# SCH_Spotify-Display_2026-06-03.net
KiCad netlist of a schematic drawn in EasyEDA
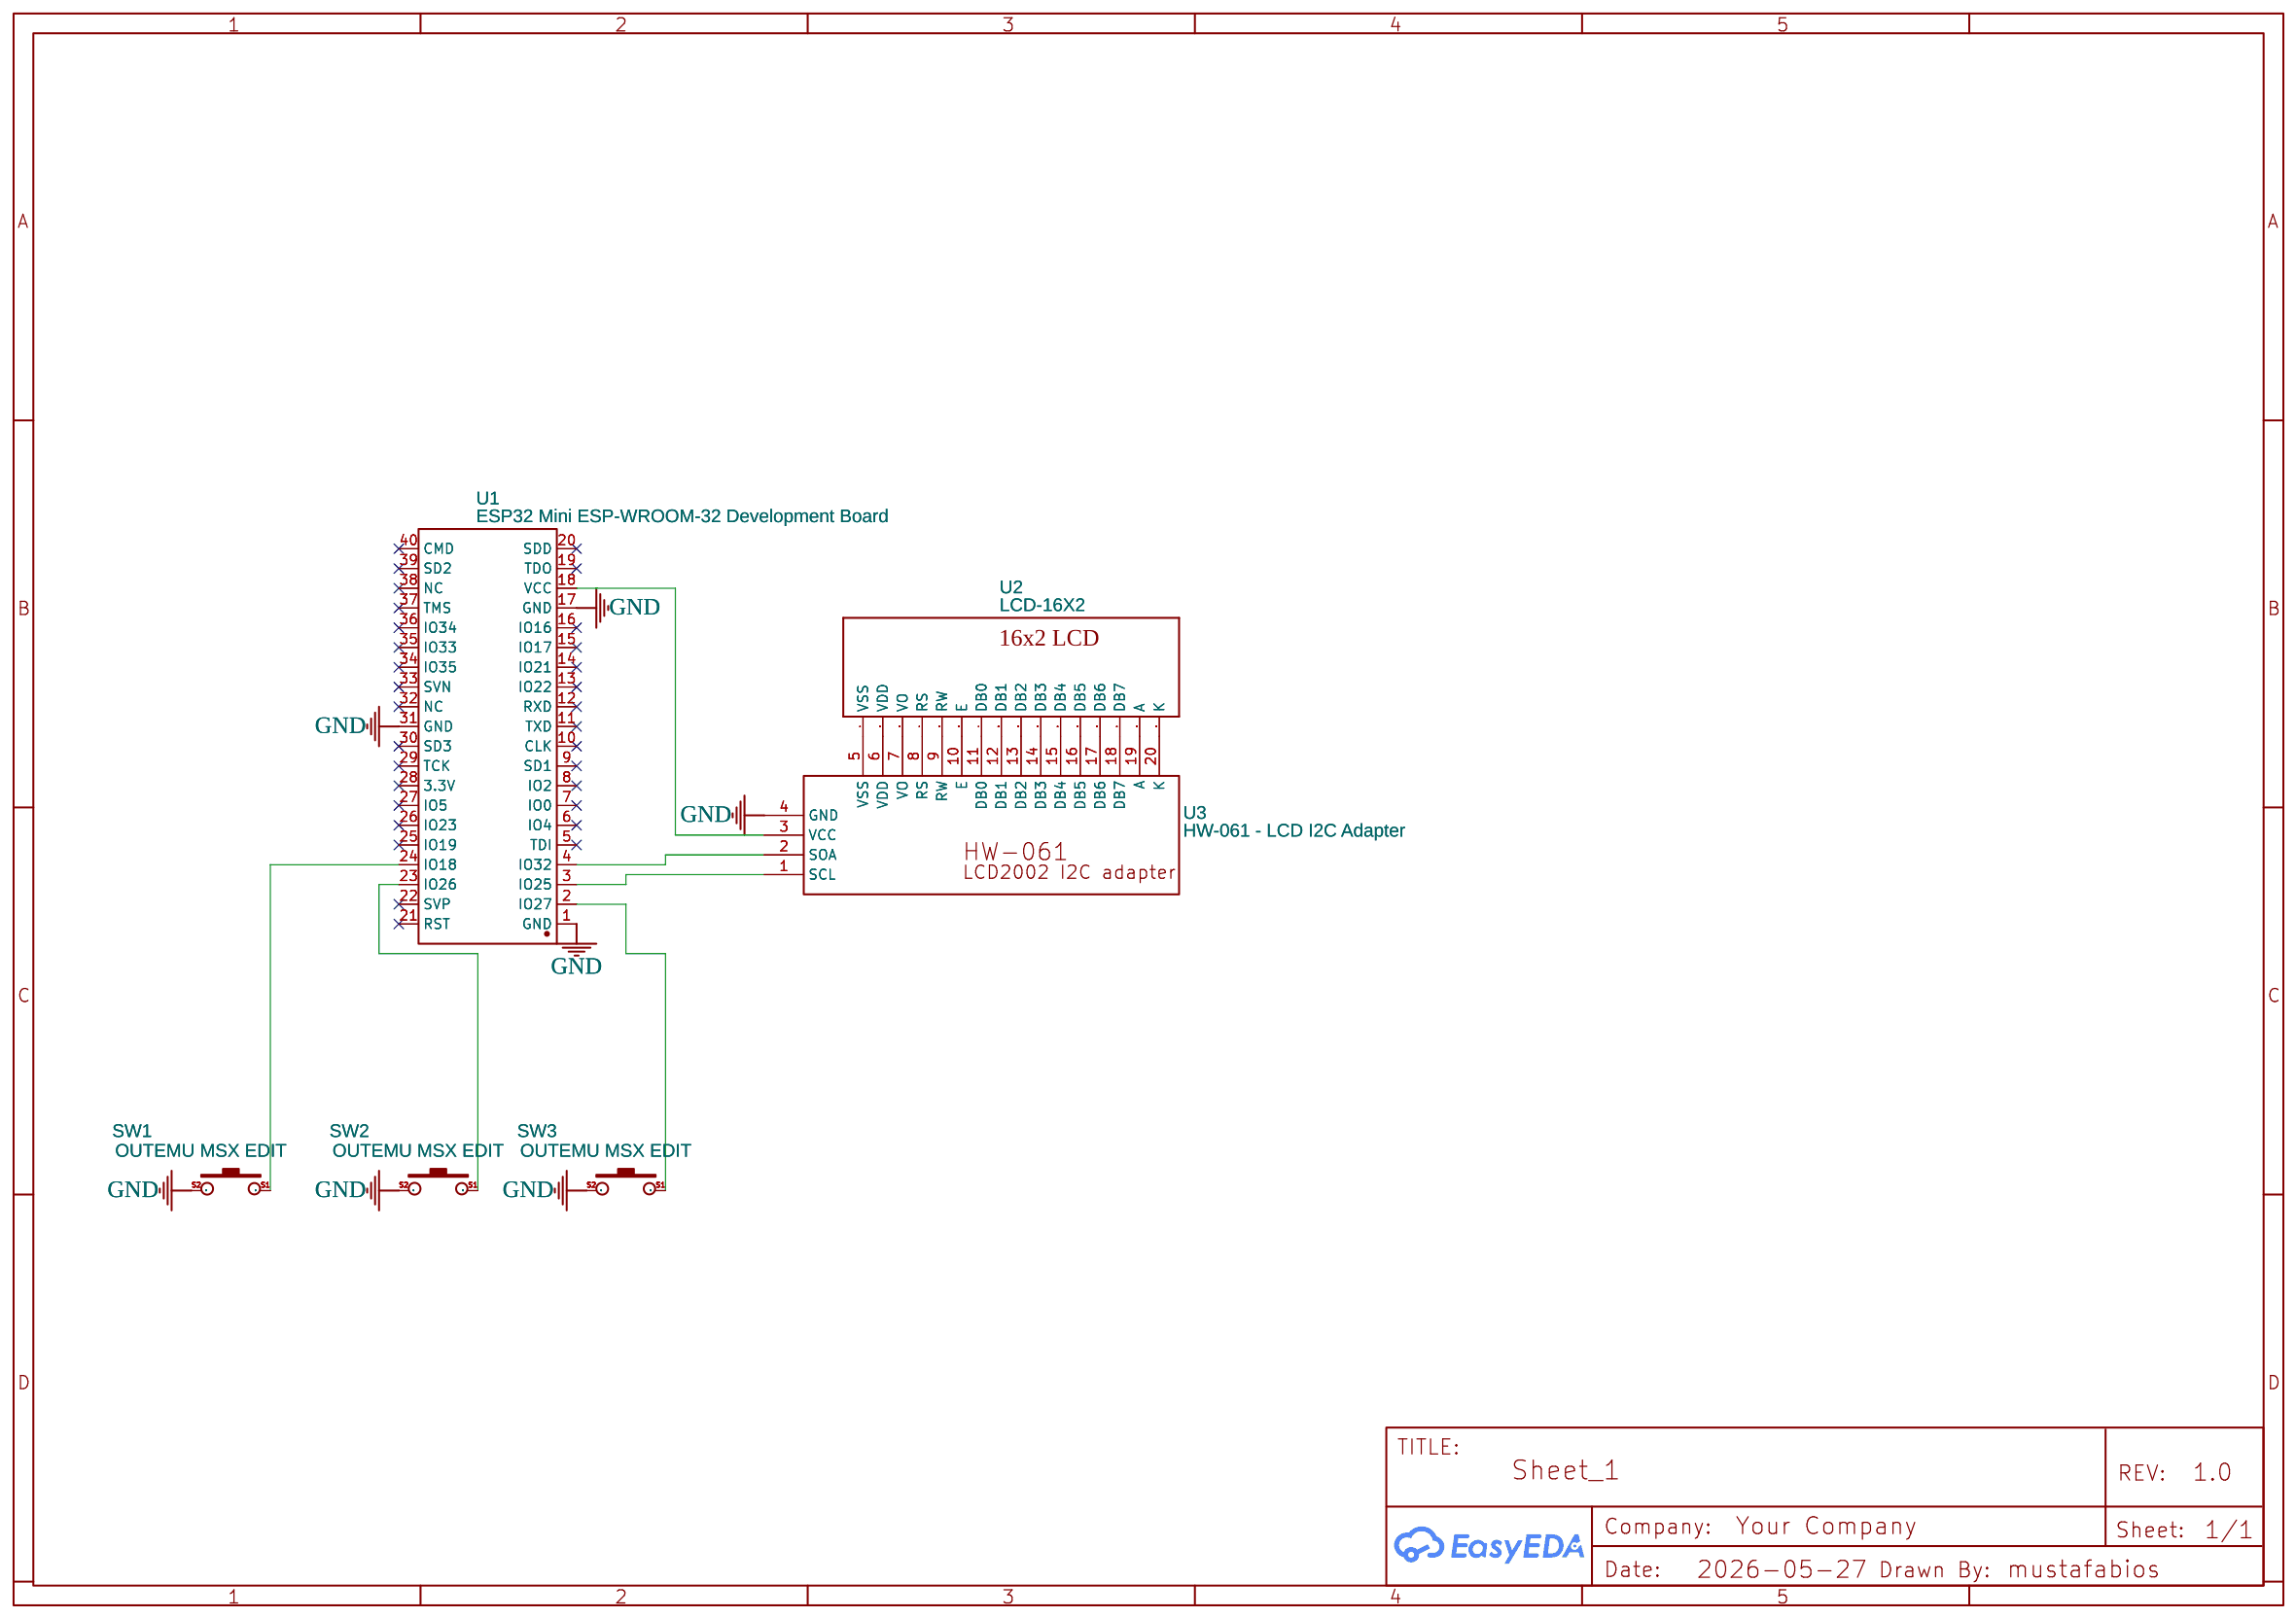
[diagram p0: schematic sheet]

(export (version "E")
  (design (tool "Eeschema 10.0.6"))
  (components
    (comp (ref "SW1") (value "OUTEMU MSX EDIT") (libsource (lib "") (part "OUTEMU MSX EDIT")))
    (comp (ref "SW2") (value "OUTEMU MSX EDIT") (libsource (lib "") (part "OUTEMU MSX EDIT")))
    (comp (ref "SW3") (value "OUTEMU MSX EDIT") (libsource (lib "") (part "OUTEMU MSX EDIT")))
    (comp (ref "U1")
      (value "ESP32 Mini ESP-WROOM-32 Development Board")
      (fields (field (name "Manufacturer Part") "B07BK435ZW") (field (name "Manufacturer") "HiLetgo"))
      (libsource (lib "") (part "ESP32 Mini ESP-WROOM-32 Development Board"))
    )
    (comp (ref "U2") (value "LCD-16X2") (libsource (lib "") (part "LCD-16X2")))
    (comp (ref "U3")
      (value "HW-061 - LCD I2C Adapter")
      (libsource (lib "") (part "HW-061 - LCD I2C Adapter"))
    )
  )
  (nets
    (net (code "1") (name "GND") (class "Default")
      (node (ref "SW1") (pin "S2") (pinfunction "S2_S2") (pintype "unspecified"))
      (node (ref "SW2") (pin "S2") (pinfunction "S2_S2") (pintype "unspecified"))
      (node (ref "SW3") (pin "S2") (pinfunction "S2_S2") (pintype "unspecified"))
      (node (ref "U1") (pin "1") (pinfunction "GND_1") (pintype "passive"))
      (node (ref "U1") (pin "17") (pinfunction "GND_17") (pintype "passive"))
      (node (ref "U1") (pin "31") (pinfunction "GND_31") (pintype "passive"))
      (node (ref "U3") (pin "4") (pinfunction "GND_4") (pintype "unspecified"))
    )
    (net (code "2") (name "Net-(U1-IO18)") (class "Default")
      (node (ref "SW1") (pin "S1") (pinfunction "S1_S1") (pintype "unspecified"))
      (node (ref "U1") (pin "24") (pinfunction "IO18_24") (pintype "bidirectional"))
    )
    (net (code "3") (name "Net-(U1-IO25)") (class "Default")
      (node (ref "U1") (pin "3") (pinfunction "IO25_3") (pintype "bidirectional"))
      (node (ref "U3") (pin "1") (pinfunction "SCL_1") (pintype "unspecified"))
    )
    (net (code "4") (name "Net-(U1-IO26)") (class "Default")
      (node (ref "SW2") (pin "S1") (pinfunction "S1_S1") (pintype "unspecified"))
      (node (ref "U1") (pin "23") (pinfunction "IO26_23") (pintype "bidirectional"))
    )
    (net (code "5") (name "Net-(U1-IO27)") (class "Default")
      (node (ref "SW3") (pin "S1") (pinfunction "S1_S1") (pintype "unspecified"))
      (node (ref "U1") (pin "2") (pinfunction "IO27_2") (pintype "bidirectional"))
    )
    (net (code "6") (name "Net-(U1-IO32)") (class "Default")
      (node (ref "U1") (pin "4") (pinfunction "IO32_4") (pintype "bidirectional"))
      (node (ref "U3") (pin "2") (pinfunction "SOA_2") (pintype "unspecified"))
    )
    (net (code "7") (name "Net-(U1-VCC)") (class "Default")
      (node (ref "U1") (pin "18") (pinfunction "VCC_18") (pintype "passive"))
      (node (ref "U3") (pin "3") (pinfunction "VCC_3") (pintype "unspecified"))
    )
    (net (code "8") (name "Net-(U2-A)") (class "Default")
      (node (ref "U2") (pin "15") (pinfunction "A_15") (pintype "passive"))
      (node (ref "U3") (pin "19") (pinfunction "A_19") (pintype "unspecified"))
    )
    (net (code "9") (name "Net-(U2-DB0)") (class "Default")
      (node (ref "U2") (pin "7") (pinfunction "DB0_7") (pintype "unspecified"))
      (node (ref "U3") (pin "11") (pinfunction "DB0_11") (pintype "unspecified"))
    )
    (net (code "10") (name "Net-(U2-DB1)") (class "Default")
      (node (ref "U2") (pin "8") (pinfunction "DB1_8") (pintype "unspecified"))
      (node (ref "U3") (pin "12") (pinfunction "DB1_12") (pintype "unspecified"))
    )
    (net (code "11") (name "Net-(U2-DB2)") (class "Default")
      (node (ref "U2") (pin "9") (pinfunction "DB2_9") (pintype "unspecified"))
      (node (ref "U3") (pin "13") (pinfunction "DB2_13") (pintype "unspecified"))
    )
    (net (code "12") (name "Net-(U2-DB3)") (class "Default")
      (node (ref "U2") (pin "10") (pinfunction "DB3_10") (pintype "unspecified"))
      (node (ref "U3") (pin "14") (pinfunction "DB3_14") (pintype "unspecified"))
    )
    (net (code "13") (name "Net-(U2-DB4)") (class "Default")
      (node (ref "U2") (pin "11") (pinfunction "DB4_11") (pintype "unspecified"))
      (node (ref "U3") (pin "15") (pinfunction "DB4_15") (pintype "unspecified"))
    )
    (net (code "14") (name "Net-(U2-DB5)") (class "Default")
      (node (ref "U2") (pin "12") (pinfunction "DB5_12") (pintype "unspecified"))
      (node (ref "U3") (pin "16") (pinfunction "DB5_16") (pintype "unspecified"))
    )
    (net (code "15") (name "Net-(U2-DB6)") (class "Default")
      (node (ref "U2") (pin "13") (pinfunction "DB6_13") (pintype "unspecified"))
      (node (ref "U3") (pin "17") (pinfunction "DB6_17") (pintype "unspecified"))
    )
    (net (code "16") (name "Net-(U2-DB7)") (class "Default")
      (node (ref "U2") (pin "14") (pinfunction "DB7_14") (pintype "unspecified"))
      (node (ref "U3") (pin "18") (pinfunction "DB7_18") (pintype "unspecified"))
    )
    (net (code "17") (name "Net-(U2-E)") (class "Default")
      (node (ref "U2") (pin "6") (pinfunction "E_6") (pintype "input"))
      (node (ref "U3") (pin "10") (pinfunction "E_10") (pintype "unspecified"))
    )
    (net (code "18") (name "Net-(U2-K)") (class "Default")
      (node (ref "U2") (pin "16") (pinfunction "K_16") (pintype "passive"))
      (node (ref "U3") (pin "20") (pinfunction "K_20") (pintype "unspecified"))
    )
    (net (code "19") (name "Net-(U2-RS)") (class "Default")
      (node (ref "U2") (pin "4") (pinfunction "RS_4") (pintype "input"))
      (node (ref "U3") (pin "8") (pinfunction "RS_8") (pintype "unspecified"))
    )
    (net (code "20") (name "Net-(U2-RW)") (class "Default")
      (node (ref "U2") (pin "5") (pinfunction "RW_5") (pintype "input"))
      (node (ref "U3") (pin "9") (pinfunction "RW_9") (pintype "unspecified"))
    )
    (net (code "21") (name "Net-(U2-VDD)") (class "Default")
      (node (ref "U2") (pin "2") (pinfunction "VDD_2") (pintype "passive"))
      (node (ref "U3") (pin "6") (pinfunction "VDD_6") (pintype "unspecified"))
    )
    (net (code "22") (name "Net-(U2-VO)") (class "Default")
      (node (ref "U2") (pin "3") (pinfunction "VO_3") (pintype "unspecified"))
      (node (ref "U3") (pin "7") (pinfunction "VO_7") (pintype "unspecified"))
    )
    (net (code "23") (name "Net-(U2-VSS)") (class "Default")
      (node (ref "U2") (pin "1") (pinfunction "VSS_1") (pintype "passive"))
      (node (ref "U3") (pin "5") (pinfunction "VSS_5") (pintype "unspecified"))
    )
    (net (code "24") (name "unconnected-(U1-3.3V-Pad28)") (class "Default")
      (node (ref "U1") (pin "28") (pinfunction "3.3V_28") (pintype "passive+no_connect"))
    )
    (net (code "25") (name "unconnected-(U1-CLK-Pad10)") (class "Default")
      (node (ref "U1") (pin "10") (pinfunction "CLK_10") (pintype "unspecified+no_connect"))
    )
    (net (code "26") (name "unconnected-(U1-CMD-Pad40)") (class "Default")
      (node (ref "U1") (pin "40") (pinfunction "CMD_40") (pintype "unspecified+no_connect"))
    )
    (net (code "27") (name "unconnected-(U1-IO0-Pad7)") (class "Default")
      (node (ref "U1") (pin "7") (pinfunction "IO0_7") (pintype "bidirectional+no_connect"))
    )
    (net (code "28") (name "unconnected-(U1-IO2-Pad8)") (class "Default")
      (node (ref "U1") (pin "8") (pinfunction "IO2_8") (pintype "bidirectional+no_connect"))
    )
    (net (code "29") (name "unconnected-(U1-IO4-Pad6)") (class "Default")
      (node (ref "U1") (pin "6") (pinfunction "IO4_6") (pintype "bidirectional+no_connect"))
    )
    (net (code "30") (name "unconnected-(U1-IO5-Pad27)") (class "Default")
      (node (ref "U1") (pin "27") (pinfunction "IO5_27") (pintype "bidirectional+no_connect"))
    )
    (net (code "31") (name "unconnected-(U1-IO16-Pad16)") (class "Default")
      (node (ref "U1") (pin "16") (pinfunction "IO16_16") (pintype "bidirectional+no_connect"))
    )
    (net (code "32") (name "unconnected-(U1-IO17-Pad15)") (class "Default")
      (node (ref "U1") (pin "15") (pinfunction "IO17_15") (pintype "bidirectional+no_connect"))
    )
    (net (code "33") (name "unconnected-(U1-IO19-Pad25)") (class "Default")
      (node (ref "U1") (pin "25") (pinfunction "IO19_25") (pintype "bidirectional+no_connect"))
    )
    (net (code "34") (name "unconnected-(U1-IO21-Pad14)") (class "Default")
      (node (ref "U1") (pin "14") (pinfunction "IO21_14") (pintype "bidirectional+no_connect"))
    )
    (net (code "35") (name "unconnected-(U1-IO22-Pad13)") (class "Default")
      (node (ref "U1") (pin "13") (pinfunction "IO22_13") (pintype "bidirectional+no_connect"))
    )
    (net (code "36") (name "unconnected-(U1-IO23-Pad26)") (class "Default")
      (node (ref "U1") (pin "26") (pinfunction "IO23_26") (pintype "bidirectional+no_connect"))
    )
    (net (code "37") (name "unconnected-(U1-IO33-Pad35)") (class "Default")
      (node (ref "U1") (pin "35") (pinfunction "IO33_35") (pintype "bidirectional+no_connect"))
    )
    (net (code "38") (name "unconnected-(U1-IO34-Pad36)") (class "Default")
      (node (ref "U1") (pin "36") (pinfunction "IO34_36") (pintype "bidirectional+no_connect"))
    )
    (net (code "39") (name "unconnected-(U1-IO35-Pad34)") (class "Default")
      (node (ref "U1") (pin "34") (pinfunction "IO35_34") (pintype "bidirectional+no_connect"))
    )
    (net (code "40") (name "unconnected-(U1-NC-Pad32)") (class "Default")
      (node (ref "U1") (pin "32") (pinfunction "NC_32") (pintype "unspecified+no_connect"))
    )
    (net (code "41") (name "unconnected-(U1-NC-Pad38)") (class "Default")
      (node (ref "U1") (pin "38") (pinfunction "NC_38") (pintype "unspecified+no_connect"))
    )
    (net (code "42") (name "unconnected-(U1-RST-Pad21)") (class "Default")
      (node (ref "U1") (pin "21") (pinfunction "RST_21") (pintype "input+no_connect"))
    )
    (net (code "43") (name "unconnected-(U1-RXD-Pad12)") (class "Default")
      (node (ref "U1") (pin "12") (pinfunction "RXD_12") (pintype "output+no_connect"))
    )
    (net (code "44") (name "unconnected-(U1-SD1-Pad9)") (class "Default")
      (node (ref "U1") (pin "9") (pinfunction "SD1_9") (pintype "unspecified+no_connect"))
    )
    (net (code "45") (name "unconnected-(U1-SD2-Pad39)") (class "Default")
      (node (ref "U1") (pin "39") (pinfunction "SD2_39") (pintype "unspecified+no_connect"))
    )
    (net (code "46") (name "unconnected-(U1-SD3-Pad30)") (class "Default")
      (node (ref "U1") (pin "30") (pinfunction "SD3_30") (pintype "unspecified+no_connect"))
    )
    (net (code "47") (name "unconnected-(U1-SDD-Pad20)") (class "Default")
      (node (ref "U1") (pin "20") (pinfunction "SDD_20") (pintype "unspecified+no_connect"))
    )
    (net (code "48") (name "unconnected-(U1-SVN-Pad33)") (class "Default")
      (node (ref "U1") (pin "33") (pinfunction "SVN_33") (pintype "unspecified+no_connect"))
    )
    (net (code "49") (name "unconnected-(U1-SVP-Pad22)") (class "Default")
      (node (ref "U1") (pin "22") (pinfunction "SVP_22") (pintype "unspecified+no_connect"))
    )
    (net (code "50") (name "unconnected-(U1-TCK-Pad29)") (class "Default")
      (node (ref "U1") (pin "29") (pinfunction "TCK_29") (pintype "unspecified+no_connect"))
    )
    (net (code "51") (name "unconnected-(U1-TDI-Pad5)") (class "Default")
      (node (ref "U1") (pin "5") (pinfunction "TDI_5") (pintype "input+no_connect"))
    )
    (net (code "52") (name "unconnected-(U1-TDO-Pad19)") (class "Default")
      (node (ref "U1") (pin "19") (pinfunction "TDO_19") (pintype "output+no_connect"))
    )
    (net (code "53") (name "unconnected-(U1-TMS-Pad37)") (class "Default")
      (node (ref "U1") (pin "37") (pinfunction "TMS_37") (pintype "unspecified+no_connect"))
    )
    (net (code "54") (name "unconnected-(U1-TXD-Pad11)") (class "Default")
      (node (ref "U1") (pin "11") (pinfunction "TXD_11") (pintype "output+no_connect"))
    )
  )
)
